# main_board.net
KiCad netlist of a schematic drawn in EAGLE
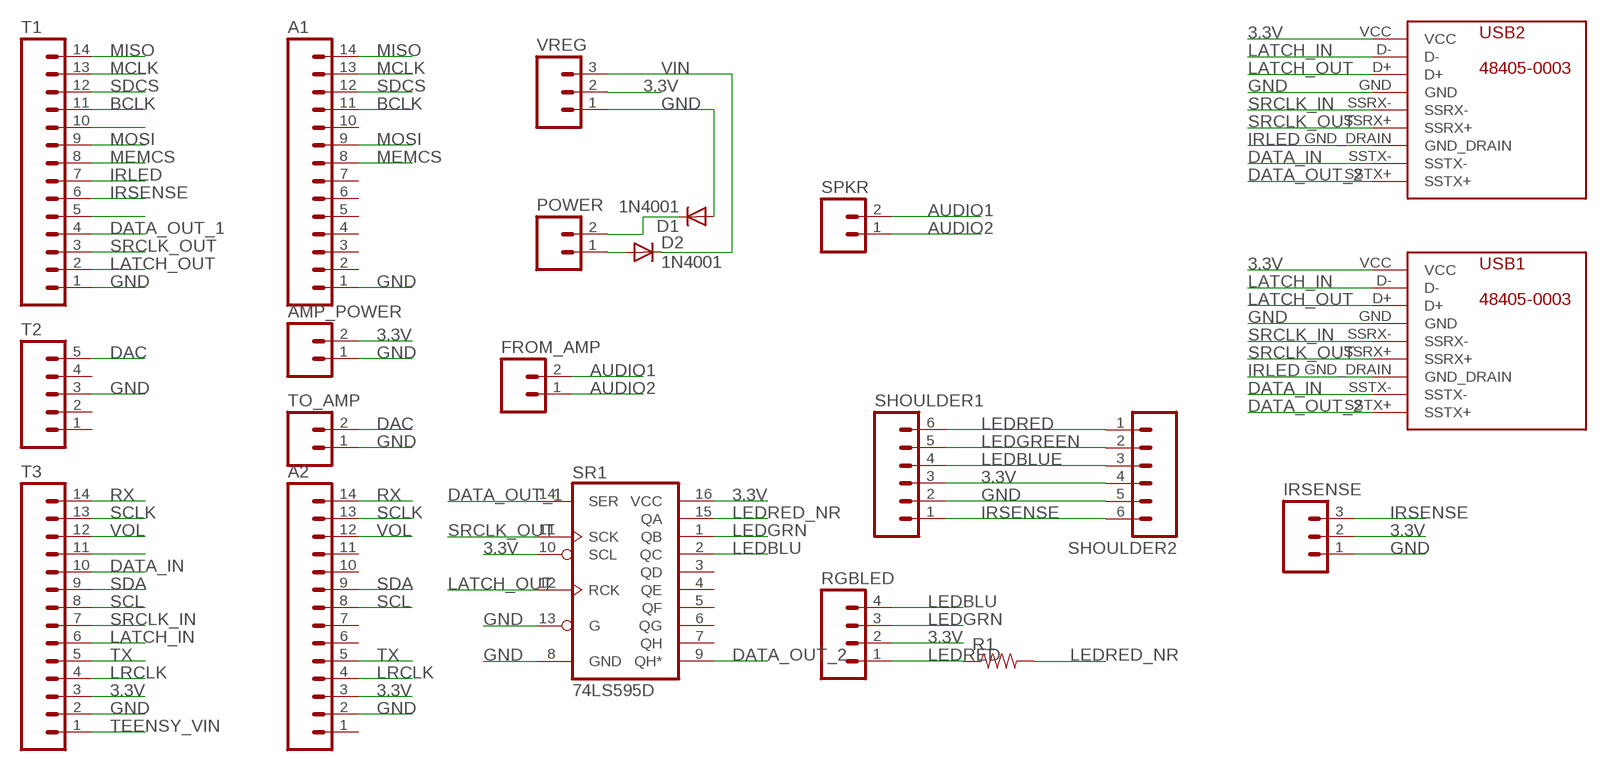
[diagram p0: schematic, sheet 1]

(export (version "E")
  (design (tool "Eeschema 10.0.6"))
  (components
    (comp (ref "A1")
      (value "M14")
      (footprint "eagle-import:1X14")
      (libsource (lib "eagle-import") (part "M14"))
    )
    (comp (ref "A2")
      (value "M14")
      (footprint "eagle-import:1X14")
      (libsource (lib "eagle-import") (part "M14"))
    )
    (comp (ref "AMP_POWER")
      (value "M02PTH")
      (footprint "eagle-import:1X02")
      (libsource (lib "eagle-import") (part "M02PTH"))
    )
    (comp (ref "D1")
      (value "1N4001")
      (footprint "eagle-import:DO41-10")
      (libsource (lib "eagle-import") (part "1N4004"))
    )
    (comp (ref "D2")
      (value "1N4001")
      (footprint "eagle-import:DO41-10")
      (libsource (lib "eagle-import") (part "1N4004"))
    )
    (comp (ref "FROM_AMP")
      (value "M02PTH")
      (footprint "eagle-import:1X02")
      (libsource (lib "eagle-import") (part "M02PTH"))
    )
    (comp (ref "IRSENSE")
      (value "M03PTH")
      (footprint "eagle-import:1X03")
      (libsource (lib "eagle-import") (part "M03PTH"))
    )
    (comp (ref "POWER")
      (value "M02PTH")
      (footprint "eagle-import:1X02")
      (libsource (lib "eagle-import") (part "M02PTH"))
    )
    (comp (ref "R1")
      (value "RESISTOR1206")
      (footprint "eagle-import:1206")
      (libsource (lib "eagle-import") (part "RESISTOR1206"))
    )
    (comp (ref "RGBLED")
      (value "M04PTH")
      (footprint "eagle-import:1X04")
      (libsource (lib "eagle-import") (part "M04PTH"))
    )
    (comp (ref "SHOULDER1")
      (value "M06SILK_FEMALE_PTH")
      (footprint "eagle-import:1X06")
      (libsource (lib "eagle-import") (part "M06SILK_FEMALE_PTH"))
    )
    (comp (ref "SHOULDER2")
      (value "M06SILK_FEMALE_PTH")
      (footprint "eagle-import:1X06")
      (libsource (lib "eagle-import") (part "M06SILK_FEMALE_PTH"))
    )
    (comp (ref "SPKR")
      (value "M02PTH")
      (footprint "eagle-import:1X02")
      (libsource (lib "eagle-import") (part "M02PTH"))
    )
    (comp (ref "SR1")
      (value "74LS595D")
      (footprint "eagle-import:SO16")
      (libsource (lib "eagle-import") (part "74595DLS"))
    )
    (comp (ref "T1")
      (value "M14")
      (footprint "eagle-import:1X14")
      (libsource (lib "eagle-import") (part "M14"))
    )
    (comp (ref "T2")
      (value "M05PTH")
      (footprint "eagle-import:1X05")
      (libsource (lib "eagle-import") (part "M05PTH"))
    )
    (comp (ref "T3")
      (value "M14")
      (footprint "eagle-import:1X14")
      (libsource (lib "eagle-import") (part "M14"))
    )
    (comp (ref "TO_AMP")
      (value "M02PTH")
      (footprint "eagle-import:1X02")
      (libsource (lib "eagle-import") (part "M02PTH"))
    )
    (comp (ref "USB1")
      (value "48405-0003")
      (footprint "eagle-import:48405-0003MYVERSION")
      (libsource (lib "eagle-import") (part "48405-0003"))
    )
    (comp (ref "USB2")
      (value "48405-0003")
      (footprint "eagle-import:48405-0003MYVERSION")
      (libsource (lib "eagle-import") (part "48405-0003"))
    )
    (comp (ref "VREG")
      (value "M03PTH")
      (footprint "eagle-import:1X03")
      (libsource (lib "eagle-import") (part "M03PTH"))
    )
  )
  (nets
    (net (code "1") (name "/3.3V") (class "Default")
      (node (ref "A2") (pin "3") (pinfunction "3_3") (pintype "passive"))
      (node (ref "AMP_POWER") (pin "2") (pinfunction "2_2") (pintype "passive"))
      (node (ref "IRSENSE") (pin "2") (pinfunction "2_2") (pintype "passive"))
      (node (ref "RGBLED") (pin "2") (pinfunction "2_2") (pintype "passive"))
      (node (ref "SHOULDER1") (pin "3") (pinfunction "3_3") (pintype "passive"))
      (node (ref "SHOULDER2") (pin "4") (pinfunction "4_4") (pintype "passive"))
      (node (ref "SR1") (pin "10") (pinfunction "SCL_10") (pintype "input"))
      (node (ref "SR1") (pin "16") (pinfunction "VCC_16") (pintype "power_in"))
      (node (ref "T3") (pin "3") (pinfunction "3_3") (pintype "passive"))
      (node (ref "USB1") (pin "VCC") (pinfunction "VCC_VCC") (pintype "bidirectional"))
      (node (ref "USB2") (pin "VCC") (pinfunction "VCC_VCC") (pintype "bidirectional"))
      (node (ref "VREG") (pin "2") (pinfunction "2_2") (pintype "passive"))
    )
    (net (code "2") (name "/AUDIO1") (class "Default")
      (node (ref "FROM_AMP") (pin "2") (pinfunction "2_2") (pintype "passive"))
      (node (ref "SPKR") (pin "2") (pinfunction "2_2") (pintype "passive"))
    )
    (net (code "3") (name "/AUDIO2") (class "Default")
      (node (ref "FROM_AMP") (pin "1") (pinfunction "1_1") (pintype "passive"))
      (node (ref "SPKR") (pin "1") (pinfunction "1_1") (pintype "passive"))
    )
    (net (code "4") (name "/BCLK") (class "Default")
      (node (ref "A1") (pin "11") (pinfunction "11_11") (pintype "passive"))
      (node (ref "T1") (pin "11") (pinfunction "11_11") (pintype "passive"))
    )
    (net (code "5") (name "/DAC") (class "Default")
      (node (ref "T2") (pin "5") (pinfunction "5_5") (pintype "passive"))
      (node (ref "TO_AMP") (pin "2") (pinfunction "2_2") (pintype "passive"))
    )
    (net (code "6") (name "/DATA_IN") (class "Default")
      (node (ref "T3") (pin "10") (pinfunction "10_10") (pintype "passive"))
      (node (ref "USB1") (pin "SSTX-") (pinfunction "SSTX-_SSTX-") (pintype "bidirectional"))
      (node (ref "USB2") (pin "SSTX-") (pinfunction "SSTX-_SSTX-") (pintype "bidirectional"))
    )
    (net (code "7") (name "/DATA_OUT_1") (class "Default")
      (node (ref "SR1") (pin "14") (pinfunction "SER_14") (pintype "input"))
      (node (ref "T1") (pin "4") (pinfunction "4_4") (pintype "passive"))
    )
    (net (code "8") (name "/DATA_OUT_2") (class "Default")
      (node (ref "SR1") (pin "9") (pinfunction "QH*_9") (pintype "tri_state"))
      (node (ref "USB1") (pin "SSTX+") (pinfunction "SSTX+_SSTX+") (pintype "bidirectional"))
      (node (ref "USB2") (pin "SSTX+") (pinfunction "SSTX+_SSTX+") (pintype "bidirectional"))
    )
    (net (code "9") (name "/GND") (class "Default")
      (node (ref "A1") (pin "1") (pinfunction "1_1") (pintype "passive"))
      (node (ref "A2") (pin "2") (pinfunction "2_2") (pintype "passive"))
      (node (ref "AMP_POWER") (pin "1") (pinfunction "1_1") (pintype "passive"))
      (node (ref "D1") (pin "A") (pinfunction "A_A") (pintype "passive"))
      (node (ref "IRSENSE") (pin "1") (pinfunction "1_1") (pintype "passive"))
      (node (ref "SHOULDER1") (pin "2") (pinfunction "2_2") (pintype "passive"))
      (node (ref "SHOULDER2") (pin "5") (pinfunction "5_5") (pintype "passive"))
      (node (ref "SR1") (pin "13") (pinfunction "G_13") (pintype "input"))
      (node (ref "SR1") (pin "8") (pinfunction "GND_8") (pintype "power_in"))
      (node (ref "T1") (pin "1") (pinfunction "1_1") (pintype "passive"))
      (node (ref "T2") (pin "3") (pinfunction "3_3") (pintype "passive"))
      (node (ref "T3") (pin "2") (pinfunction "2_2") (pintype "passive"))
      (node (ref "TO_AMP") (pin "1") (pinfunction "1_1") (pintype "passive"))
      (node (ref "USB1") (pin "GND") (pinfunction "GND_GND") (pintype "bidirectional"))
      (node (ref "USB2") (pin "GND") (pinfunction "GND_GND") (pintype "bidirectional"))
      (node (ref "VREG") (pin "1") (pinfunction "1_1") (pintype "passive"))
    )
    (net (code "10") (name "/IRLED") (class "Default")
      (node (ref "T1") (pin "7") (pinfunction "7_7") (pintype "passive"))
      (node (ref "USB1") (pin "GND_DRAIN") (pinfunction "GND_DRAIN_GND_DRAIN") (pintype "bidirectional"))
      (node (ref "USB2") (pin "GND_DRAIN") (pinfunction "GND_DRAIN_GND_DRAIN") (pintype "bidirectional"))
    )
    (net (code "11") (name "/IRSENSE") (class "Default")
      (node (ref "IRSENSE") (pin "3") (pinfunction "3_3") (pintype "passive"))
      (node (ref "SHOULDER1") (pin "1") (pinfunction "1_1") (pintype "passive"))
      (node (ref "SHOULDER2") (pin "6") (pinfunction "6_6") (pintype "passive"))
      (node (ref "T1") (pin "6") (pinfunction "6_6") (pintype "passive"))
    )
    (net (code "12") (name "/LATCH_IN") (class "Default")
      (node (ref "T3") (pin "6") (pinfunction "6_6") (pintype "passive"))
      (node (ref "USB1") (pin "D-") (pinfunction "D-_D-") (pintype "bidirectional"))
      (node (ref "USB2") (pin "D-") (pinfunction "D-_D-") (pintype "bidirectional"))
    )
    (net (code "13") (name "/LATCH_OUT") (class "Default")
      (node (ref "SR1") (pin "12") (pinfunction "RCK_12") (pintype "input"))
      (node (ref "T1") (pin "2") (pinfunction "2_2") (pintype "passive"))
      (node (ref "USB1") (pin "D+") (pinfunction "D+_D+") (pintype "bidirectional"))
      (node (ref "USB2") (pin "D+") (pinfunction "D+_D+") (pintype "bidirectional"))
    )
    (net (code "14") (name "/LEDBLU") (class "Default")
      (node (ref "RGBLED") (pin "4") (pinfunction "4_4") (pintype "passive"))
      (node (ref "SR1") (pin "2") (pinfunction "QC_2") (pintype "tri_state"))
    )
    (net (code "15") (name "/LEDBLUE") (class "Default")
      (node (ref "SHOULDER1") (pin "4") (pinfunction "4_4") (pintype "passive"))
      (node (ref "SHOULDER2") (pin "3") (pinfunction "3_3") (pintype "passive"))
    )
    (net (code "16") (name "/LEDGREEN") (class "Default")
      (node (ref "SHOULDER1") (pin "5") (pinfunction "5_5") (pintype "passive"))
      (node (ref "SHOULDER2") (pin "2") (pinfunction "2_2") (pintype "passive"))
    )
    (net (code "17") (name "/LEDGRN") (class "Default")
      (node (ref "RGBLED") (pin "3") (pinfunction "3_3") (pintype "passive"))
      (node (ref "SR1") (pin "1") (pinfunction "QB_1") (pintype "tri_state"))
    )
    (net (code "18") (name "/LEDRED") (class "Default")
      (node (ref "R1") (pin "1") (pinfunction "1_1") (pintype "passive"))
      (node (ref "RGBLED") (pin "1") (pinfunction "1_1") (pintype "passive"))
      (node (ref "SHOULDER1") (pin "6") (pinfunction "6_6") (pintype "passive"))
      (node (ref "SHOULDER2") (pin "1") (pinfunction "1_1") (pintype "passive"))
    )
    (net (code "19") (name "/LEDRED_NR") (class "Default")
      (node (ref "R1") (pin "2") (pinfunction "2_2") (pintype "passive"))
      (node (ref "SR1") (pin "15") (pinfunction "QA_15") (pintype "tri_state"))
    )
    (net (code "20") (name "/LRCLK") (class "Default")
      (node (ref "A2") (pin "4") (pinfunction "4_4") (pintype "passive"))
      (node (ref "T3") (pin "4") (pinfunction "4_4") (pintype "passive"))
    )
    (net (code "21") (name "/MCLK") (class "Default")
      (node (ref "A1") (pin "13") (pinfunction "13_13") (pintype "passive"))
      (node (ref "T1") (pin "13") (pinfunction "13_13") (pintype "passive"))
    )
    (net (code "22") (name "/MEMCS") (class "Default")
      (node (ref "A1") (pin "8") (pinfunction "8_8") (pintype "passive"))
      (node (ref "T1") (pin "8") (pinfunction "8_8") (pintype "passive"))
    )
    (net (code "23") (name "/MISO") (class "Default")
      (node (ref "A1") (pin "14") (pinfunction "14_14") (pintype "passive"))
      (node (ref "T1") (pin "14") (pinfunction "14_14") (pintype "passive"))
    )
    (net (code "24") (name "/MOSI") (class "Default")
      (node (ref "A1") (pin "9") (pinfunction "9_9") (pintype "passive"))
      (node (ref "T1") (pin "9") (pinfunction "9_9") (pintype "passive"))
    )
    (net (code "25") (name "/RX") (class "Default")
      (node (ref "A2") (pin "14") (pinfunction "14_14") (pintype "passive"))
      (node (ref "T3") (pin "14") (pinfunction "14_14") (pintype "passive"))
    )
    (net (code "26") (name "/SCL") (class "Default")
      (node (ref "A2") (pin "8") (pinfunction "8_8") (pintype "passive"))
      (node (ref "T3") (pin "8") (pinfunction "8_8") (pintype "passive"))
    )
    (net (code "27") (name "/SCLK") (class "Default")
      (node (ref "A2") (pin "13") (pinfunction "13_13") (pintype "passive"))
      (node (ref "T3") (pin "13") (pinfunction "13_13") (pintype "passive"))
    )
    (net (code "28") (name "/SDA") (class "Default")
      (node (ref "A2") (pin "9") (pinfunction "9_9") (pintype "passive"))
      (node (ref "T3") (pin "9") (pinfunction "9_9") (pintype "passive"))
    )
    (net (code "29") (name "/SDCS") (class "Default")
      (node (ref "A1") (pin "12") (pinfunction "12_12") (pintype "passive"))
      (node (ref "T1") (pin "12") (pinfunction "12_12") (pintype "passive"))
    )
    (net (code "30") (name "/SRCLK_IN") (class "Default")
      (node (ref "T3") (pin "7") (pinfunction "7_7") (pintype "passive"))
      (node (ref "USB1") (pin "SSRX-") (pinfunction "SSRX-_SSRX-") (pintype "bidirectional"))
      (node (ref "USB2") (pin "SSRX-") (pinfunction "SSRX-_SSRX-") (pintype "bidirectional"))
    )
    (net (code "31") (name "/SRCLK_OUT") (class "Default")
      (node (ref "SR1") (pin "11") (pinfunction "SCK_11") (pintype "input"))
      (node (ref "T1") (pin "3") (pinfunction "3_3") (pintype "passive"))
      (node (ref "USB1") (pin "SSRX+") (pinfunction "SSRX+_SSRX+") (pintype "bidirectional"))
      (node (ref "USB2") (pin "SSRX+") (pinfunction "SSRX+_SSRX+") (pintype "bidirectional"))
    )
    (net (code "32") (name "/TEENSY_VIN") (class "Default")
      (node (ref "T3") (pin "1") (pinfunction "1_1") (pintype "passive"))
    )
    (net (code "33") (name "/TX") (class "Default")
      (node (ref "A2") (pin "5") (pinfunction "5_5") (pintype "passive"))
      (node (ref "T3") (pin "5") (pinfunction "5_5") (pintype "passive"))
    )
    (net (code "34") (name "/VIN") (class "Default")
      (node (ref "D2") (pin "C") (pinfunction "C_C") (pintype "passive"))
      (node (ref "VREG") (pin "3") (pinfunction "3_3") (pintype "passive"))
    )
    (net (code "35") (name "/VOL") (class "Default")
      (node (ref "A2") (pin "12") (pinfunction "12_12") (pintype "passive"))
      (node (ref "T3") (pin "12") (pinfunction "12_12") (pintype "passive"))
    )
    (net (code "36") (name "Net-(D1-PadC)") (class "Default")
      (node (ref "D1") (pin "C") (pinfunction "C_C") (pintype "passive"))
      (node (ref "POWER") (pin "2") (pinfunction "2_2") (pintype "passive"))
    )
    (net (code "37") (name "Net-(D2-PadA)") (class "Default")
      (node (ref "D2") (pin "A") (pinfunction "A_A") (pintype "passive"))
      (node (ref "POWER") (pin "1") (pinfunction "1_1") (pintype "passive"))
    )
    (net (code "38") (name "unconnected-(A1-Pad2)") (class "Default")
      (node (ref "A1") (pin "2") (pinfunction "2_2") (pintype "passive"))
    )
    (net (code "39") (name "unconnected-(A1-Pad3)") (class "Default")
      (node (ref "A1") (pin "3") (pinfunction "3_3") (pintype "passive"))
    )
    (net (code "40") (name "unconnected-(A1-Pad4)") (class "Default")
      (node (ref "A1") (pin "4") (pinfunction "4_4") (pintype "passive"))
    )
    (net (code "41") (name "unconnected-(A1-Pad5)") (class "Default")
      (node (ref "A1") (pin "5") (pinfunction "5_5") (pintype "passive"))
    )
    (net (code "42") (name "unconnected-(A1-Pad6)") (class "Default")
      (node (ref "A1") (pin "6") (pinfunction "6_6") (pintype "passive"))
    )
    (net (code "43") (name "unconnected-(A1-Pad7)") (class "Default")
      (node (ref "A1") (pin "7") (pinfunction "7_7") (pintype "passive"))
    )
    (net (code "44") (name "unconnected-(A1-Pad10)") (class "Default")
      (node (ref "A1") (pin "10") (pinfunction "10_10") (pintype "passive"))
    )
    (net (code "45") (name "unconnected-(A2-Pad1)") (class "Default")
      (node (ref "A2") (pin "1") (pinfunction "1_1") (pintype "passive"))
    )
    (net (code "46") (name "unconnected-(A2-Pad6)") (class "Default")
      (node (ref "A2") (pin "6") (pinfunction "6_6") (pintype "passive"))
    )
    (net (code "47") (name "unconnected-(A2-Pad7)") (class "Default")
      (node (ref "A2") (pin "7") (pinfunction "7_7") (pintype "passive"))
    )
    (net (code "48") (name "unconnected-(A2-Pad10)") (class "Default")
      (node (ref "A2") (pin "10") (pinfunction "10_10") (pintype "passive"))
    )
    (net (code "49") (name "unconnected-(A2-Pad11)") (class "Default")
      (node (ref "A2") (pin "11") (pinfunction "11_11") (pintype "passive"))
    )
    (net (code "50") (name "unconnected-(SR1-QD-Pad3)") (class "Default")
      (node (ref "SR1") (pin "3") (pinfunction "QD_3") (pintype "tri_state"))
    )
    (net (code "51") (name "unconnected-(SR1-QE-Pad4)") (class "Default")
      (node (ref "SR1") (pin "4") (pinfunction "QE_4") (pintype "tri_state"))
    )
    (net (code "52") (name "unconnected-(SR1-QF-Pad5)") (class "Default")
      (node (ref "SR1") (pin "5") (pinfunction "QF_5") (pintype "tri_state"))
    )
    (net (code "53") (name "unconnected-(SR1-QG-Pad6)") (class "Default")
      (node (ref "SR1") (pin "6") (pinfunction "QG_6") (pintype "tri_state"))
    )
    (net (code "54") (name "unconnected-(SR1-QH-Pad7)") (class "Default")
      (node (ref "SR1") (pin "7") (pinfunction "QH_7") (pintype "tri_state"))
    )
    (net (code "55") (name "unconnected-(T1-Pad5)") (class "Default")
      (node (ref "T1") (pin "5") (pinfunction "5_5") (pintype "passive"))
    )
    (net (code "56") (name "unconnected-(T1-Pad10)") (class "Default")
      (node (ref "T1") (pin "10") (pinfunction "10_10") (pintype "passive"))
    )
    (net (code "57") (name "unconnected-(T2-Pad1)") (class "Default")
      (node (ref "T2") (pin "1") (pinfunction "1_1") (pintype "passive"))
    )
    (net (code "58") (name "unconnected-(T2-Pad2)") (class "Default")
      (node (ref "T2") (pin "2") (pinfunction "2_2") (pintype "passive"))
    )
    (net (code "59") (name "unconnected-(T2-Pad4)") (class "Default")
      (node (ref "T2") (pin "4") (pinfunction "4_4") (pintype "passive"))
    )
    (net (code "60") (name "unconnected-(T3-Pad11)") (class "Default")
      (node (ref "T3") (pin "11") (pinfunction "11_11") (pintype "passive"))
    )
  )
)
